# CMV4000.net
KiCad netlist of a schematic drawn in Altium Designer
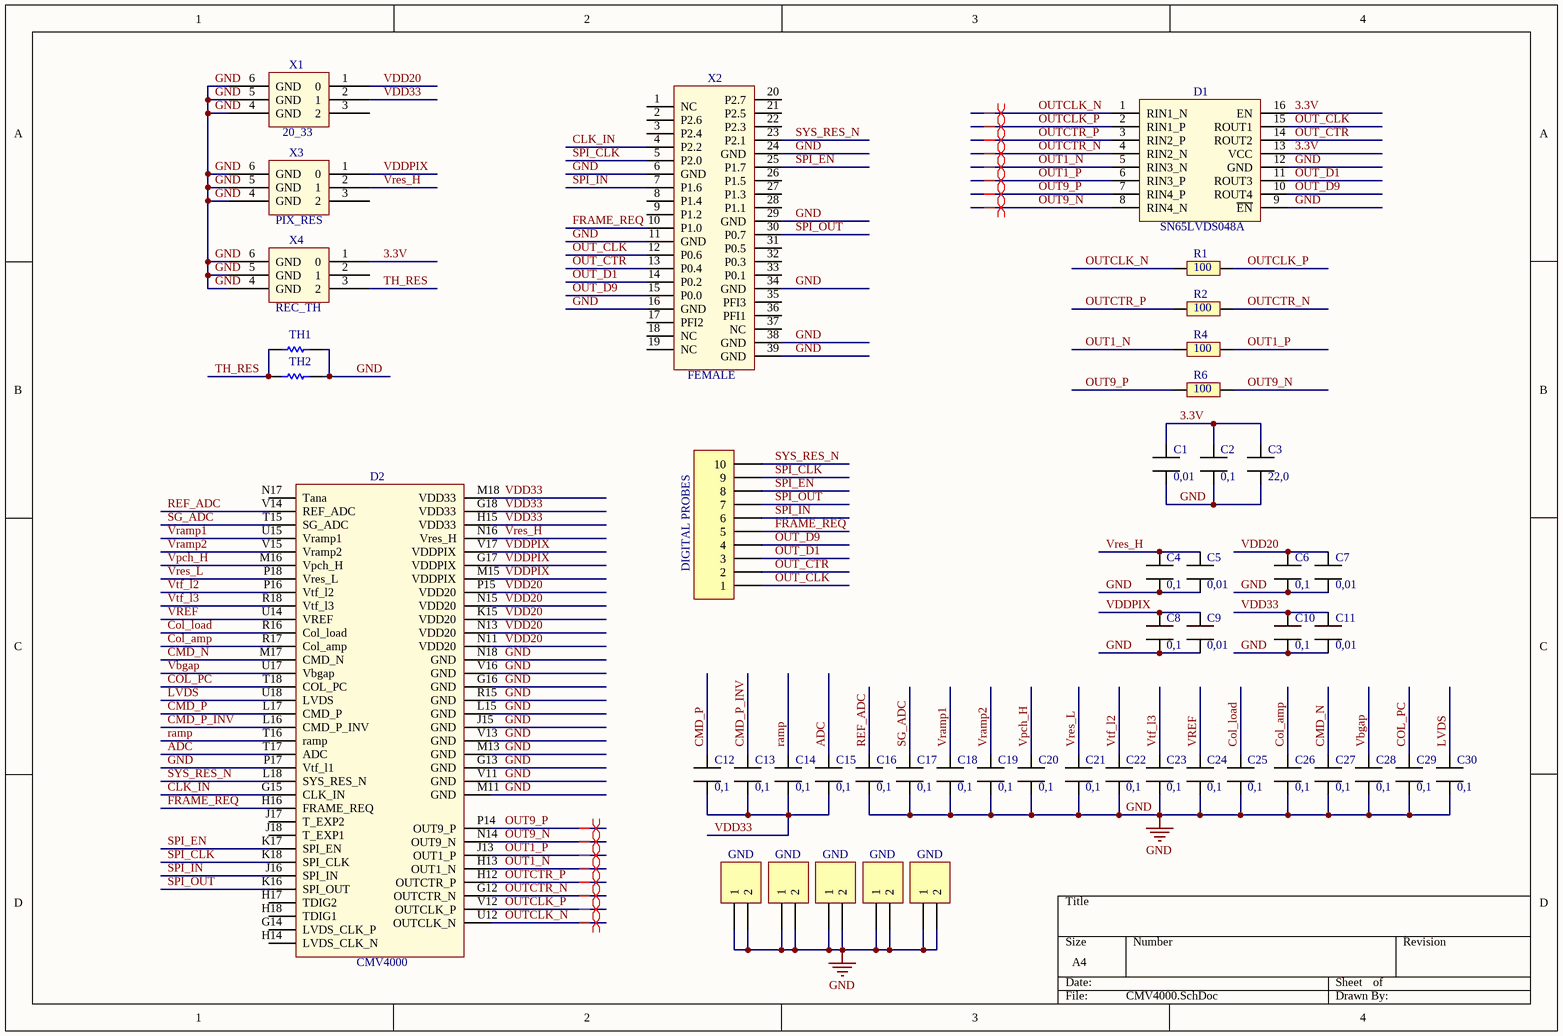
[diagram p0: CMV4000.SchDoc]

(export (version "E")
  (design (tool "Eeschema 10.0.6"))
  (components
    (comp (ref "C1") (value "0,01") (footprint "CAP_SMALL") (libsource (lib "Schlib") (part "CAP_SMALL")))
    (comp (ref "C2") (value "0,1") (footprint "CAP_SMALL") (libsource (lib "Schlib") (part "CAP_SMALL")))
    (comp (ref "C3") (value "22,0") (footprint "Cap_BIG") (libsource (lib "Schlib") (part "CAP_BIG")))
    (comp (ref "C4") (value "0,1") (footprint "CAP_SMALL") (libsource (lib "Schlib") (part "CAP_SMALL")))
    (comp (ref "C5") (value "0,01") (footprint "CAP_SMALL") (libsource (lib "Schlib") (part "CAP_SMALL")))
    (comp (ref "C6") (value "0,1") (footprint "CAP_SMALL") (libsource (lib "Schlib") (part "CAP_SMALL")))
    (comp (ref "C7") (value "0,01") (footprint "CAP_SMALL") (libsource (lib "Schlib") (part "CAP_SMALL")))
    (comp (ref "C8") (value "0,1") (footprint "CAP_SMALL") (libsource (lib "Schlib") (part "CAP_SMALL")))
    (comp (ref "C9") (value "0,01") (footprint "CAP_SMALL") (libsource (lib "Schlib") (part "CAP_SMALL")))
    (comp (ref "C10") (value "0,1") (footprint "CAP_SMALL") (libsource (lib "Schlib") (part "CAP_SMALL")))
    (comp (ref "C11") (value "0,01") (footprint "CAP_SMALL") (libsource (lib "Schlib") (part "CAP_SMALL")))
    (comp (ref "C12") (value "0,1") (footprint "CAP_SMALL") (libsource (lib "Schlib") (part "CAP_SMALL")))
    (comp (ref "C13") (value "0,1") (footprint "CAP_SMALL") (libsource (lib "Schlib") (part "CAP_SMALL")))
    (comp (ref "C14") (value "0,1") (footprint "CAP_SMALL") (libsource (lib "Schlib") (part "CAP_SMALL")))
    (comp (ref "C15") (value "0,1") (footprint "CAP_SMALL") (libsource (lib "Schlib") (part "CAP_SMALL")))
    (comp (ref "C16") (value "0,1") (footprint "CAP_SMALL") (libsource (lib "Schlib") (part "CAP_SMALL")))
    (comp (ref "C17") (value "0,1") (footprint "CAP_SMALL") (libsource (lib "Schlib") (part "CAP_SMALL")))
    (comp (ref "C18") (value "0,1") (footprint "CAP_SMALL") (libsource (lib "Schlib") (part "CAP_SMALL")))
    (comp (ref "C19") (value "0,1") (footprint "CAP_SMALL") (libsource (lib "Schlib") (part "CAP_SMALL")))
    (comp (ref "C20") (value "0,1") (footprint "CAP_SMALL") (libsource (lib "Schlib") (part "CAP_SMALL")))
    (comp (ref "C21") (value "0,1") (footprint "CAP_SMALL") (libsource (lib "Schlib") (part "CAP_SMALL")))
    (comp (ref "C22") (value "0,1") (footprint "CAP_SMALL") (libsource (lib "Schlib") (part "CAP_SMALL")))
    (comp (ref "C23") (value "0,1") (footprint "CAP_SMALL") (libsource (lib "Schlib") (part "CAP_SMALL")))
    (comp (ref "C24") (value "0,1") (footprint "CAP_SMALL") (libsource (lib "Schlib") (part "CAP_SMALL")))
    (comp (ref "C25") (value "0,1") (footprint "CAP_SMALL") (libsource (lib "Schlib") (part "CAP_SMALL")))
    (comp (ref "C26") (value "0,1") (footprint "CAP_SMALL") (libsource (lib "Schlib") (part "CAP_SMALL")))
    (comp (ref "C27") (value "0,1") (footprint "CAP_SMALL") (libsource (lib "Schlib") (part "CAP_SMALL")))
    (comp (ref "C28") (value "0,1") (footprint "CAP_SMALL") (libsource (lib "Schlib") (part "CAP_SMALL")))
    (comp (ref "C29") (value "0,1") (footprint "CAP_SMALL") (libsource (lib "Schlib") (part "CAP_SMALL")))
    (comp (ref "C30") (value "0,1") (footprint "CAP_SMALL") (libsource (lib "Schlib") (part "CAP_SMALL")))
    (comp (ref "D1")
      (value "SN65LVDS048A")
      (footprint "SN65LVDS048A (4LVDS)")
      (libsource (lib "Schlib") (part "SN65LVDS048A (4LVDS)"))
    )
    (comp (ref "D2") (value "CMV4000") (footprint "SOCKET_AM2") (libsource (lib "Schlib") (part "CMV4000")))
    (comp (ref "P1")
      (value "GND")
      (footprint "HDR1X2")
      (description "Header, 2-Pin")
      (fields (field (name "PUBLISHER") "Altium Limited"))
      (libsource (lib "Miscellaneous Connectors") (part "Header 2"))
    )
    (comp (ref "P2")
      (value "GND")
      (footprint "HDR1X2")
      (description "Header, 2-Pin")
      (fields (field (name "PUBLISHER") "Altium Limited"))
      (libsource (lib "Miscellaneous Connectors") (part "Header 2"))
    )
    (comp (ref "P3")
      (value "GND")
      (footprint "HDR1X2")
      (description "Header, 2-Pin")
      (fields (field (name "PUBLISHER") "Altium Limited"))
      (libsource (lib "Miscellaneous Connectors") (part "Header 2"))
    )
    (comp (ref "P4")
      (value "GND")
      (footprint "HDR1X2")
      (description "Header, 2-Pin")
      (fields (field (name "PUBLISHER") "Altium Limited"))
      (libsource (lib "Miscellaneous Connectors") (part "Header 2"))
    )
    (comp (ref "P5")
      (value "GND")
      (footprint "HDR1X2")
      (description "Header, 2-Pin")
      (fields (field (name "PUBLISHER") "Altium Limited"))
      (libsource (lib "Miscellaneous Connectors") (part "Header 2"))
    )
    (comp (ref "P6")
      (value "DIGITAL PROBES")
      (footprint "HDR1X10")
      (description "Header, 10-Pin")
      (fields (field (name "PUBLISHER") "Altium Limited"))
      (libsource (lib "Miscellaneous Connectors") (part "Header 10"))
    )
    (comp (ref "R1") (value "100") (footprint "RES") (libsource (lib "Schlib") (part "RES")))
    (comp (ref "R2") (value "100") (footprint "RES") (libsource (lib "Schlib") (part "RES")))
    (comp (ref "R4") (value "100") (footprint "RES") (libsource (lib "Schlib") (part "RES")))
    (comp (ref "R6") (value "100") (footprint "RES") (libsource (lib "Schlib") (part "RES")))
    (comp (ref "TH1")
      (value "Res Semi")
      (footprint "AXIAL-0.5")
      (description "Semiconductor Resistor")
      (fields (field (name "PUBLISHER") "Altium Limited"))
      (libsource (lib "Miscellaneous Devices") (part "Res Semi"))
    )
    (comp (ref "TH2")
      (value "Res Semi")
      (footprint "AXIAL-0.5")
      (description "Semiconductor Resistor")
      (fields (field (name "PUBLISHER") "Altium Limited"))
      (libsource (lib "Miscellaneous Devices") (part "Res Semi"))
    )
    (comp (ref "X1") (value "20_33") (footprint "POWER") (libsource (lib "Schlib") (part "POWER")))
    (comp (ref "X2")
      (value "FEMALE")
      (footprint "CHEAP_CONN_FEMALE")
      (libsource (lib "Schlib") (part "CHEAP_CON_37_FEMALE"))
    )
    (comp (ref "X3") (value "PIX_RES") (footprint "POWER") (libsource (lib "Schlib") (part "POWER")))
    (comp (ref "X4") (value "REC_TH") (footprint "POWER") (libsource (lib "Schlib") (part "POWER")))
  )
  (nets
    (net (code "1") (name "/3.3V") (class "Default")
      (node (ref "C1") (pin "2") (pinfunction "2_2") (pintype "passive"))
      (node (ref "C2") (pin "2") (pinfunction "2_2") (pintype "passive"))
      (node (ref "C3") (pin "2") (pinfunction "2_2") (pintype "passive"))
      (node (ref "D1") (pin "13") (pinfunction "VCC_13") (pintype "passive"))
      (node (ref "D1") (pin "16") (pinfunction "EN_16") (pintype "passive"))
      (node (ref "X4") (pin "1") (pinfunction "0_1") (pintype "passive"))
    )
    (net (code "2") (name "/ADC") (class "Default")
      (node (ref "C15") (pin "2") (pinfunction "2_2") (pintype "passive"))
      (node (ref "D2") (pin "T17") (pinfunction "ADC_T17") (pintype "passive"))
    )
    (net (code "3") (name "/CLK_IN") (class "Default")
      (node (ref "D2") (pin "G15") (pinfunction "CLK_IN_G15") (pintype "passive"))
      (node (ref "X2") (pin "4") (pinfunction "P2.2_4") (pintype "passive"))
    )
    (net (code "4") (name "/CMD_N") (class "Default")
      (node (ref "C27") (pin "2") (pinfunction "2_2") (pintype "passive"))
      (node (ref "D2") (pin "M17") (pinfunction "CMD_N_M17") (pintype "passive"))
    )
    (net (code "5") (name "/CMD_P") (class "Default")
      (node (ref "C12") (pin "2") (pinfunction "2_2") (pintype "passive"))
      (node (ref "D2") (pin "L17") (pinfunction "CMD_P_L17") (pintype "passive"))
    )
    (net (code "6") (name "/CMD_P_INV") (class "Default")
      (node (ref "C13") (pin "2") (pinfunction "2_2") (pintype "passive"))
      (node (ref "D2") (pin "L16") (pinfunction "CMD_P_INV_L16") (pintype "passive"))
    )
    (net (code "7") (name "/COL_PC") (class "Default")
      (node (ref "C29") (pin "2") (pinfunction "2_2") (pintype "passive"))
      (node (ref "D2") (pin "T18") (pinfunction "COL_PC_T18") (pintype "passive"))
    )
    (net (code "8") (name "/Col_amp") (class "Default")
      (node (ref "C26") (pin "2") (pinfunction "2_2") (pintype "passive"))
      (node (ref "D2") (pin "R17") (pinfunction "Col_amp_R17") (pintype "passive"))
    )
    (net (code "9") (name "/Col_load") (class "Default")
      (node (ref "C25") (pin "2") (pinfunction "2_2") (pintype "passive"))
      (node (ref "D2") (pin "R16") (pinfunction "Col_load_R16") (pintype "passive"))
    )
    (net (code "10") (name "/FRAME_REQ") (class "Default")
      (node (ref "D2") (pin "H16") (pinfunction "FRAME_REQ_H16") (pintype "passive"))
      (node (ref "P6") (pin "5") (pinfunction "5_5") (pintype "passive"))
      (node (ref "X2") (pin "10") (pinfunction "P1.0_10") (pintype "passive"))
    )
    (net (code "11") (name "/LVDS") (class "Default")
      (node (ref "C30") (pin "2") (pinfunction "2_2") (pintype "passive"))
      (node (ref "D2") (pin "U18") (pinfunction "LVDS_U18") (pintype "passive"))
    )
    (net (code "12") (name "/OUT1_N") (class "Default")
      (node (ref "D1") (pin "5") (pinfunction "RIN3_N_5") (pintype "passive"))
      (node (ref "D2") (pin "H13") (pinfunction "OUT1_N_H13") (pintype "passive"))
      (node (ref "R4") (pin "1") (pinfunction "1_1") (pintype "passive"))
    )
    (net (code "13") (name "/OUT1_P") (class "Default")
      (node (ref "D1") (pin "6") (pinfunction "RIN3_P_6") (pintype "passive"))
      (node (ref "D2") (pin "J13") (pinfunction "OUT1_P_J13") (pintype "passive"))
      (node (ref "R4") (pin "2") (pinfunction "2_2") (pintype "passive"))
    )
    (net (code "14") (name "/OUT9_N") (class "Default")
      (node (ref "D1") (pin "8") (pinfunction "RIN4_N_8") (pintype "passive"))
      (node (ref "D2") (pin "N14") (pinfunction "OUT9_N_N14") (pintype "passive"))
      (node (ref "R6") (pin "2") (pinfunction "2_2") (pintype "passive"))
    )
    (net (code "15") (name "/OUT9_P") (class "Default")
      (node (ref "D1") (pin "7") (pinfunction "RIN4_P_7") (pintype "passive"))
      (node (ref "D2") (pin "P14") (pinfunction "OUT9_P_P14") (pintype "passive"))
      (node (ref "R6") (pin "1") (pinfunction "1_1") (pintype "passive"))
    )
    (net (code "16") (name "/OUTCLK_N") (class "Default")
      (node (ref "D1") (pin "1") (pinfunction "RIN1_N_1") (pintype "passive"))
      (node (ref "D2") (pin "U12") (pinfunction "OUTCLK_N_U12") (pintype "passive"))
      (node (ref "R1") (pin "1") (pinfunction "1_1") (pintype "passive"))
    )
    (net (code "17") (name "/OUTCLK_P") (class "Default")
      (node (ref "D1") (pin "2") (pinfunction "RIN1_P_2") (pintype "passive"))
      (node (ref "D2") (pin "V12") (pinfunction "OUTCLK_P_V12") (pintype "passive"))
      (node (ref "R1") (pin "2") (pinfunction "2_2") (pintype "passive"))
    )
    (net (code "18") (name "/OUTCTR_N") (class "Default")
      (node (ref "D1") (pin "4") (pinfunction "RIN2_N_4") (pintype "passive"))
      (node (ref "D2") (pin "G12") (pinfunction "OUTCTR_N_G12") (pintype "passive"))
      (node (ref "R2") (pin "2") (pinfunction "2_2") (pintype "passive"))
    )
    (net (code "19") (name "/OUTCTR_P") (class "Default")
      (node (ref "D1") (pin "3") (pinfunction "RIN2_P_3") (pintype "passive"))
      (node (ref "D2") (pin "H12") (pinfunction "OUTCTR_P_H12") (pintype "passive"))
      (node (ref "R2") (pin "1") (pinfunction "1_1") (pintype "passive"))
    )
    (net (code "20") (name "/OUT_CLK") (class "Default")
      (node (ref "D1") (pin "15") (pinfunction "ROUT1_15") (pintype "passive"))
      (node (ref "P6") (pin "1") (pinfunction "1_1") (pintype "passive"))
      (node (ref "X2") (pin "12") (pinfunction "P0.6_12") (pintype "passive"))
    )
    (net (code "21") (name "/OUT_CTR") (class "Default")
      (node (ref "D1") (pin "14") (pinfunction "ROUT2_14") (pintype "passive"))
      (node (ref "P6") (pin "2") (pinfunction "2_2") (pintype "passive"))
      (node (ref "X2") (pin "13") (pinfunction "P0.4_13") (pintype "passive"))
    )
    (net (code "22") (name "/OUT_D1") (class "Default")
      (node (ref "D1") (pin "11") (pinfunction "ROUT3_11") (pintype "passive"))
      (node (ref "P6") (pin "3") (pinfunction "3_3") (pintype "passive"))
      (node (ref "X2") (pin "14") (pinfunction "P0.2_14") (pintype "passive"))
    )
    (net (code "23") (name "/OUT_D9") (class "Default")
      (node (ref "D1") (pin "10") (pinfunction "ROUT4_10") (pintype "passive"))
      (node (ref "P6") (pin "4") (pinfunction "4_4") (pintype "passive"))
      (node (ref "X2") (pin "15") (pinfunction "P0.0_15") (pintype "passive"))
    )
    (net (code "24") (name "/REF_ADC") (class "Default")
      (node (ref "C16") (pin "2") (pinfunction "2_2") (pintype "passive"))
      (node (ref "D2") (pin "V14") (pinfunction "REF_ADC_V14") (pintype "passive"))
    )
    (net (code "25") (name "/SG_ADC") (class "Default")
      (node (ref "C17") (pin "2") (pinfunction "2_2") (pintype "passive"))
      (node (ref "D2") (pin "T15") (pinfunction "SG_ADC_T15") (pintype "passive"))
    )
    (net (code "26") (name "/SPI_CLK") (class "Default")
      (node (ref "D2") (pin "K18") (pinfunction "SPI_CLK_K18") (pintype "passive"))
      (node (ref "P6") (pin "9") (pinfunction "9_9") (pintype "passive"))
      (node (ref "X2") (pin "5") (pinfunction "P2.0_5") (pintype "passive"))
    )
    (net (code "27") (name "/SPI_EN") (class "Default")
      (node (ref "D2") (pin "K17") (pinfunction "SPI_EN_K17") (pintype "passive"))
      (node (ref "P6") (pin "8") (pinfunction "8_8") (pintype "passive"))
      (node (ref "X2") (pin "25") (pinfunction "P1.7_25") (pintype "passive"))
    )
    (net (code "28") (name "/SPI_IN") (class "Default")
      (node (ref "D2") (pin "J16") (pinfunction "SPI_IN_J16") (pintype "passive"))
      (node (ref "P6") (pin "6") (pinfunction "6_6") (pintype "passive"))
      (node (ref "X2") (pin "7") (pinfunction "P1.6_7") (pintype "passive"))
    )
    (net (code "29") (name "/SPI_OUT") (class "Default")
      (node (ref "D2") (pin "K16") (pinfunction "SPI_OUT_K16") (pintype "passive"))
      (node (ref "P6") (pin "7") (pinfunction "7_7") (pintype "passive"))
      (node (ref "X2") (pin "30") (pinfunction "P0.7_30") (pintype "passive"))
    )
    (net (code "30") (name "/SYS_RES_N") (class "Default")
      (node (ref "D2") (pin "L18") (pinfunction "SYS_RES_N_L18") (pintype "passive"))
      (node (ref "P6") (pin "10") (pinfunction "10_10") (pintype "passive"))
      (node (ref "X2") (pin "23") (pinfunction "P2.1_23") (pintype "passive"))
    )
    (net (code "31") (name "/TH_RES") (class "Default")
      (node (ref "TH1") (pin "1") (pinfunction "1_1") (pintype "passive"))
      (node (ref "TH2") (pin "1") (pinfunction "1_1") (pintype "passive"))
      (node (ref "X4") (pin "3") (pinfunction "2_3") (pintype "passive"))
    )
    (net (code "32") (name "/VDD20") (class "Default")
      (node (ref "C6") (pin "2") (pinfunction "2_2") (pintype "passive"))
      (node (ref "C7") (pin "2") (pinfunction "2_2") (pintype "passive"))
      (node (ref "D2") (pin "K15") (pinfunction "VDD20_K15") (pintype "passive"))
      (node (ref "D2") (pin "N11") (pinfunction "VDD20_N11") (pintype "passive"))
      (node (ref "D2") (pin "N13") (pinfunction "VDD20_N13") (pintype "passive"))
      (node (ref "D2") (pin "N15") (pinfunction "VDD20_N15") (pintype "passive"))
      (node (ref "D2") (pin "P15") (pinfunction "VDD20_P15") (pintype "passive"))
      (node (ref "X1") (pin "1") (pinfunction "0_1") (pintype "passive"))
    )
    (net (code "33") (name "/VDD33") (class "Default")
      (node (ref "C10") (pin "2") (pinfunction "2_2") (pintype "passive"))
      (node (ref "C11") (pin "2") (pinfunction "2_2") (pintype "passive"))
      (node (ref "C12") (pin "1") (pinfunction "1_1") (pintype "passive"))
      (node (ref "C13") (pin "1") (pinfunction "1_1") (pintype "passive"))
      (node (ref "C14") (pin "1") (pinfunction "1_1") (pintype "passive"))
      (node (ref "C15") (pin "1") (pinfunction "1_1") (pintype "passive"))
      (node (ref "D2") (pin "G18") (pinfunction "VDD33_G18") (pintype "passive"))
      (node (ref "D2") (pin "H15") (pinfunction "VDD33_H15") (pintype "passive"))
      (node (ref "D2") (pin "M18") (pinfunction "VDD33_M18") (pintype "passive"))
      (node (ref "X1") (pin "2") (pinfunction "1_2") (pintype "passive"))
    )
    (net (code "34") (name "/VDDPIX") (class "Default")
      (node (ref "C8") (pin "2") (pinfunction "2_2") (pintype "passive"))
      (node (ref "C9") (pin "2") (pinfunction "2_2") (pintype "passive"))
      (node (ref "D2") (pin "G17") (pinfunction "VDDPIX_G17") (pintype "passive"))
      (node (ref "D2") (pin "M15") (pinfunction "VDDPIX_M15") (pintype "passive"))
      (node (ref "D2") (pin "V17") (pinfunction "VDDPIX_V17") (pintype "passive"))
      (node (ref "X3") (pin "1") (pinfunction "0_1") (pintype "passive"))
    )
    (net (code "35") (name "/VREF") (class "Default")
      (node (ref "C24") (pin "2") (pinfunction "2_2") (pintype "passive"))
      (node (ref "D2") (pin "U14") (pinfunction "VREF_U14") (pintype "passive"))
    )
    (net (code "36") (name "/Vbgap") (class "Default")
      (node (ref "C28") (pin "2") (pinfunction "2_2") (pintype "passive"))
      (node (ref "D2") (pin "U17") (pinfunction "Vbgap_U17") (pintype "passive"))
    )
    (net (code "37") (name "/Vpch_H") (class "Default")
      (node (ref "C20") (pin "2") (pinfunction "2_2") (pintype "passive"))
      (node (ref "D2") (pin "M16") (pinfunction "Vpch_H_M16") (pintype "passive"))
    )
    (net (code "38") (name "/Vramp1") (class "Default")
      (node (ref "C18") (pin "2") (pinfunction "2_2") (pintype "passive"))
      (node (ref "D2") (pin "U15") (pinfunction "Vramp1_U15") (pintype "passive"))
    )
    (net (code "39") (name "/Vramp2") (class "Default")
      (node (ref "C19") (pin "2") (pinfunction "2_2") (pintype "passive"))
      (node (ref "D2") (pin "V15") (pinfunction "Vramp2_V15") (pintype "passive"))
    )
    (net (code "40") (name "/Vres_H") (class "Default")
      (node (ref "C4") (pin "2") (pinfunction "2_2") (pintype "passive"))
      (node (ref "C5") (pin "2") (pinfunction "2_2") (pintype "passive"))
      (node (ref "D2") (pin "N16") (pinfunction "Vres_H_N16") (pintype "passive"))
      (node (ref "X3") (pin "2") (pinfunction "1_2") (pintype "passive"))
    )
    (net (code "41") (name "/Vres_L") (class "Default")
      (node (ref "C21") (pin "2") (pinfunction "2_2") (pintype "passive"))
      (node (ref "D2") (pin "P18") (pinfunction "Vres_L_P18") (pintype "passive"))
    )
    (net (code "42") (name "/Vtf_l2") (class "Default")
      (node (ref "C22") (pin "2") (pinfunction "2_2") (pintype "passive"))
      (node (ref "D2") (pin "P16") (pinfunction "Vtf_l2_P16") (pintype "passive"))
    )
    (net (code "43") (name "/Vtf_l3") (class "Default")
      (node (ref "C23") (pin "2") (pinfunction "2_2") (pintype "passive"))
      (node (ref "D2") (pin "R18") (pinfunction "Vtf_l3_R18") (pintype "passive"))
    )
    (net (code "44") (name "/ramp") (class "Default")
      (node (ref "C14") (pin "2") (pinfunction "2_2") (pintype "passive"))
      (node (ref "D2") (pin "T16") (pinfunction "ramp_T16") (pintype "passive"))
    )
    (net (code "45") (name "GND") (class "Default")
      (node (ref "C1") (pin "1") (pinfunction "1_1") (pintype "passive"))
      (node (ref "C10") (pin "1") (pinfunction "1_1") (pintype "passive"))
      (node (ref "C11") (pin "1") (pinfunction "1_1") (pintype "passive"))
      (node (ref "C16") (pin "1") (pinfunction "1_1") (pintype "passive"))
      (node (ref "C17") (pin "1") (pinfunction "1_1") (pintype "passive"))
      (node (ref "C18") (pin "1") (pinfunction "1_1") (pintype "passive"))
      (node (ref "C19") (pin "1") (pinfunction "1_1") (pintype "passive"))
      (node (ref "C2") (pin "1") (pinfunction "1_1") (pintype "passive"))
      (node (ref "C20") (pin "1") (pinfunction "1_1") (pintype "passive"))
      (node (ref "C21") (pin "1") (pinfunction "1_1") (pintype "passive"))
      (node (ref "C22") (pin "1") (pinfunction "1_1") (pintype "passive"))
      (node (ref "C23") (pin "1") (pinfunction "1_1") (pintype "passive"))
      (node (ref "C24") (pin "1") (pinfunction "1_1") (pintype "passive"))
      (node (ref "C25") (pin "1") (pinfunction "1_1") (pintype "passive"))
      (node (ref "C26") (pin "1") (pinfunction "1_1") (pintype "passive"))
      (node (ref "C27") (pin "1") (pinfunction "1_1") (pintype "passive"))
      (node (ref "C28") (pin "1") (pinfunction "1_1") (pintype "passive"))
      (node (ref "C29") (pin "1") (pinfunction "1_1") (pintype "passive"))
      (node (ref "C3") (pin "1") (pinfunction "1_1") (pintype "passive"))
      (node (ref "C30") (pin "1") (pinfunction "1_1") (pintype "passive"))
      (node (ref "C4") (pin "1") (pinfunction "1_1") (pintype "passive"))
      (node (ref "C5") (pin "1") (pinfunction "1_1") (pintype "passive"))
      (node (ref "C6") (pin "1") (pinfunction "1_1") (pintype "passive"))
      (node (ref "C7") (pin "1") (pinfunction "1_1") (pintype "passive"))
      (node (ref "C8") (pin "1") (pinfunction "1_1") (pintype "passive"))
      (node (ref "C9") (pin "1") (pinfunction "1_1") (pintype "passive"))
      (node (ref "D1") (pin "12") (pinfunction "GND_12") (pintype "passive"))
      (node (ref "D1") (pin "9") (pinfunction "~{EN}_9") (pintype "passive"))
      (node (ref "D2") (pin "G13") (pinfunction "GND_G13") (pintype "passive"))
      (node (ref "D2") (pin "G16") (pinfunction "GND_G16") (pintype "passive"))
      (node (ref "D2") (pin "J15") (pinfunction "GND_J15") (pintype "passive"))
      (node (ref "D2") (pin "L15") (pinfunction "GND_L15") (pintype "passive"))
      (node (ref "D2") (pin "M11") (pinfunction "GND_M11") (pintype "passive"))
      (node (ref "D2") (pin "M13") (pinfunction "GND_M13") (pintype "passive"))
      (node (ref "D2") (pin "N18") (pinfunction "GND_N18") (pintype "passive"))
      (node (ref "D2") (pin "P17") (pinfunction "Vtf_l1_P17") (pintype "passive"))
      (node (ref "D2") (pin "R15") (pinfunction "GND_R15") (pintype "passive"))
      (node (ref "D2") (pin "V11") (pinfunction "GND_V11") (pintype "passive"))
      (node (ref "D2") (pin "V13") (pinfunction "GND_V13") (pintype "passive"))
      (node (ref "D2") (pin "V16") (pinfunction "GND_V16") (pintype "passive"))
      (node (ref "P1") (pin "1") (pinfunction "1_1") (pintype "passive"))
      (node (ref "P1") (pin "2") (pinfunction "2_2") (pintype "passive"))
      (node (ref "P2") (pin "1") (pinfunction "1_1") (pintype "passive"))
      (node (ref "P2") (pin "2") (pinfunction "2_2") (pintype "passive"))
      (node (ref "P3") (pin "1") (pinfunction "1_1") (pintype "passive"))
      (node (ref "P3") (pin "2") (pinfunction "2_2") (pintype "passive"))
      (node (ref "P4") (pin "1") (pinfunction "1_1") (pintype "passive"))
      (node (ref "P4") (pin "2") (pinfunction "2_2") (pintype "passive"))
      (node (ref "P5") (pin "1") (pinfunction "1_1") (pintype "passive"))
      (node (ref "P5") (pin "2") (pinfunction "2_2") (pintype "passive"))
      (node (ref "TH1") (pin "2") (pinfunction "2_2") (pintype "passive"))
      (node (ref "TH2") (pin "2") (pinfunction "2_2") (pintype "passive"))
      (node (ref "X1") (pin "4") (pinfunction "GND_4") (pintype "passive"))
      (node (ref "X1") (pin "5") (pinfunction "GND_5") (pintype "passive"))
      (node (ref "X1") (pin "6") (pinfunction "GND_6") (pintype "passive"))
      (node (ref "X2") (pin "11") (pinfunction "GND_11") (pintype "passive"))
      (node (ref "X2") (pin "16") (pinfunction "GND_16") (pintype "passive"))
      (node (ref "X2") (pin "24") (pinfunction "GND_24") (pintype "passive"))
      (node (ref "X2") (pin "29") (pinfunction "GND_29") (pintype "passive"))
      (node (ref "X2") (pin "34") (pinfunction "GND_34") (pintype "passive"))
      (node (ref "X2") (pin "38") (pinfunction "GND_38") (pintype "passive"))
      (node (ref "X2") (pin "39") (pinfunction "GND_39") (pintype "passive"))
      (node (ref "X2") (pin "6") (pinfunction "GND_6") (pintype "passive"))
      (node (ref "X3") (pin "4") (pinfunction "GND_4") (pintype "passive"))
      (node (ref "X3") (pin "5") (pinfunction "GND_5") (pintype "passive"))
      (node (ref "X3") (pin "6") (pinfunction "GND_6") (pintype "passive"))
      (node (ref "X4") (pin "4") (pinfunction "GND_4") (pintype "passive"))
      (node (ref "X4") (pin "5") (pinfunction "GND_5") (pintype "passive"))
      (node (ref "X4") (pin "6") (pinfunction "GND_6") (pintype "passive"))
    )
    (net (code "46") (name "unconnected-(D2-LVDS_CLK_N-PadH14)") (class "Default")
      (node (ref "D2") (pin "H14") (pinfunction "LVDS_CLK_N_H14") (pintype "passive"))
    )
    (net (code "47") (name "unconnected-(D2-LVDS_CLK_P-PadG14)") (class "Default")
      (node (ref "D2") (pin "G14") (pinfunction "LVDS_CLK_P_G14") (pintype "passive"))
    )
    (net (code "48") (name "unconnected-(D2-TDIG1-PadH18)") (class "Default")
      (node (ref "D2") (pin "H18") (pinfunction "TDIG1_H18") (pintype "passive"))
    )
    (net (code "49") (name "unconnected-(D2-TDIG2-PadH17)") (class "Default")
      (node (ref "D2") (pin "H17") (pinfunction "TDIG2_H17") (pintype "passive"))
    )
    (net (code "50") (name "unconnected-(D2-T_EXP1-PadJ18)") (class "Default")
      (node (ref "D2") (pin "J18") (pinfunction "T_EXP1_J18") (pintype "passive"))
    )
    (net (code "51") (name "unconnected-(D2-T_EXP2-PadJ17)") (class "Default")
      (node (ref "D2") (pin "J17") (pinfunction "T_EXP2_J17") (pintype "passive"))
    )
    (net (code "52") (name "unconnected-(D2-Tana-PadN17)") (class "Default")
      (node (ref "D2") (pin "N17") (pinfunction "Tana_N17") (pintype "passive"))
    )
    (net (code "53") (name "unconnected-(X1-2-Pad3)") (class "Default")
      (node (ref "X1") (pin "3") (pinfunction "2_3") (pintype "passive"))
    )
    (net (code "54") (name "unconnected-(X2-NC-Pad1)") (class "Default")
      (node (ref "X2") (pin "1") (pinfunction "NC_1") (pintype "passive"))
    )
    (net (code "55") (name "unconnected-(X2-NC-Pad18)") (class "Default")
      (node (ref "X2") (pin "18") (pinfunction "NC_18") (pintype "passive"))
    )
    (net (code "56") (name "unconnected-(X2-NC-Pad19)") (class "Default")
      (node (ref "X2") (pin "19") (pinfunction "NC_19") (pintype "passive"))
    )
    (net (code "57") (name "unconnected-(X2-NC-Pad37)") (class "Default")
      (node (ref "X2") (pin "37") (pinfunction "NC_37") (pintype "passive"))
    )
    (net (code "58") (name "unconnected-(X2-P0.1-Pad33)") (class "Default")
      (node (ref "X2") (pin "33") (pinfunction "P0.1_33") (pintype "passive"))
    )
    (net (code "59") (name "unconnected-(X2-P0.3-Pad32)") (class "Default")
      (node (ref "X2") (pin "32") (pinfunction "P0.3_32") (pintype "passive"))
    )
    (net (code "60") (name "unconnected-(X2-P0.5-Pad31)") (class "Default")
      (node (ref "X2") (pin "31") (pinfunction "P0.5_31") (pintype "passive"))
    )
    (net (code "61") (name "unconnected-(X2-P1.1-Pad28)") (class "Default")
      (node (ref "X2") (pin "28") (pinfunction "P1.1_28") (pintype "passive"))
    )
    (net (code "62") (name "unconnected-(X2-P1.2-Pad9)") (class "Default")
      (node (ref "X2") (pin "9") (pinfunction "P1.2_9") (pintype "passive"))
    )
    (net (code "63") (name "unconnected-(X2-P1.3-Pad27)") (class "Default")
      (node (ref "X2") (pin "27") (pinfunction "P1.3_27") (pintype "passive"))
    )
    (net (code "64") (name "unconnected-(X2-P1.4-Pad8)") (class "Default")
      (node (ref "X2") (pin "8") (pinfunction "P1.4_8") (pintype "passive"))
    )
    (net (code "65") (name "unconnected-(X2-P1.5-Pad26)") (class "Default")
      (node (ref "X2") (pin "26") (pinfunction "P1.5_26") (pintype "passive"))
    )
    (net (code "66") (name "unconnected-(X2-P2.3-Pad22)") (class "Default")
      (node (ref "X2") (pin "22") (pinfunction "P2.3_22") (pintype "passive"))
    )
    (net (code "67") (name "unconnected-(X2-P2.4-Pad3)") (class "Default")
      (node (ref "X2") (pin "3") (pinfunction "P2.4_3") (pintype "passive"))
    )
    (net (code "68") (name "unconnected-(X2-P2.5-Pad21)") (class "Default")
      (node (ref "X2") (pin "21") (pinfunction "P2.5_21") (pintype "passive"))
    )
    (net (code "69") (name "unconnected-(X2-P2.6-Pad2)") (class "Default")
      (node (ref "X2") (pin "2") (pinfunction "P2.6_2") (pintype "passive"))
    )
    (net (code "70") (name "unconnected-(X2-P2.7-Pad20)") (class "Default")
      (node (ref "X2") (pin "20") (pinfunction "P2.7_20") (pintype "passive"))
    )
    (net (code "71") (name "unconnected-(X2-PFI1-Pad36)") (class "Default")
      (node (ref "X2") (pin "36") (pinfunction "PFI1_36") (pintype "passive"))
    )
    (net (code "72") (name "unconnected-(X2-PFI2-Pad17)") (class "Default")
      (node (ref "X2") (pin "17") (pinfunction "PFI2_17") (pintype "passive"))
    )
    (net (code "73") (name "unconnected-(X2-PFI3-Pad35)") (class "Default")
      (node (ref "X2") (pin "35") (pinfunction "PFI3_35") (pintype "passive"))
    )
    (net (code "74") (name "unconnected-(X3-2-Pad3)") (class "Default")
      (node (ref "X3") (pin "3") (pinfunction "2_3") (pintype "passive"))
    )
    (net (code "75") (name "unconnected-(X4-1-Pad2)") (class "Default")
      (node (ref "X4") (pin "2") (pinfunction "1_2") (pintype "passive"))
    )
  )
)
